# IsolatorPower.net
KiCad netlist of a schematic drawn in Altium Designer
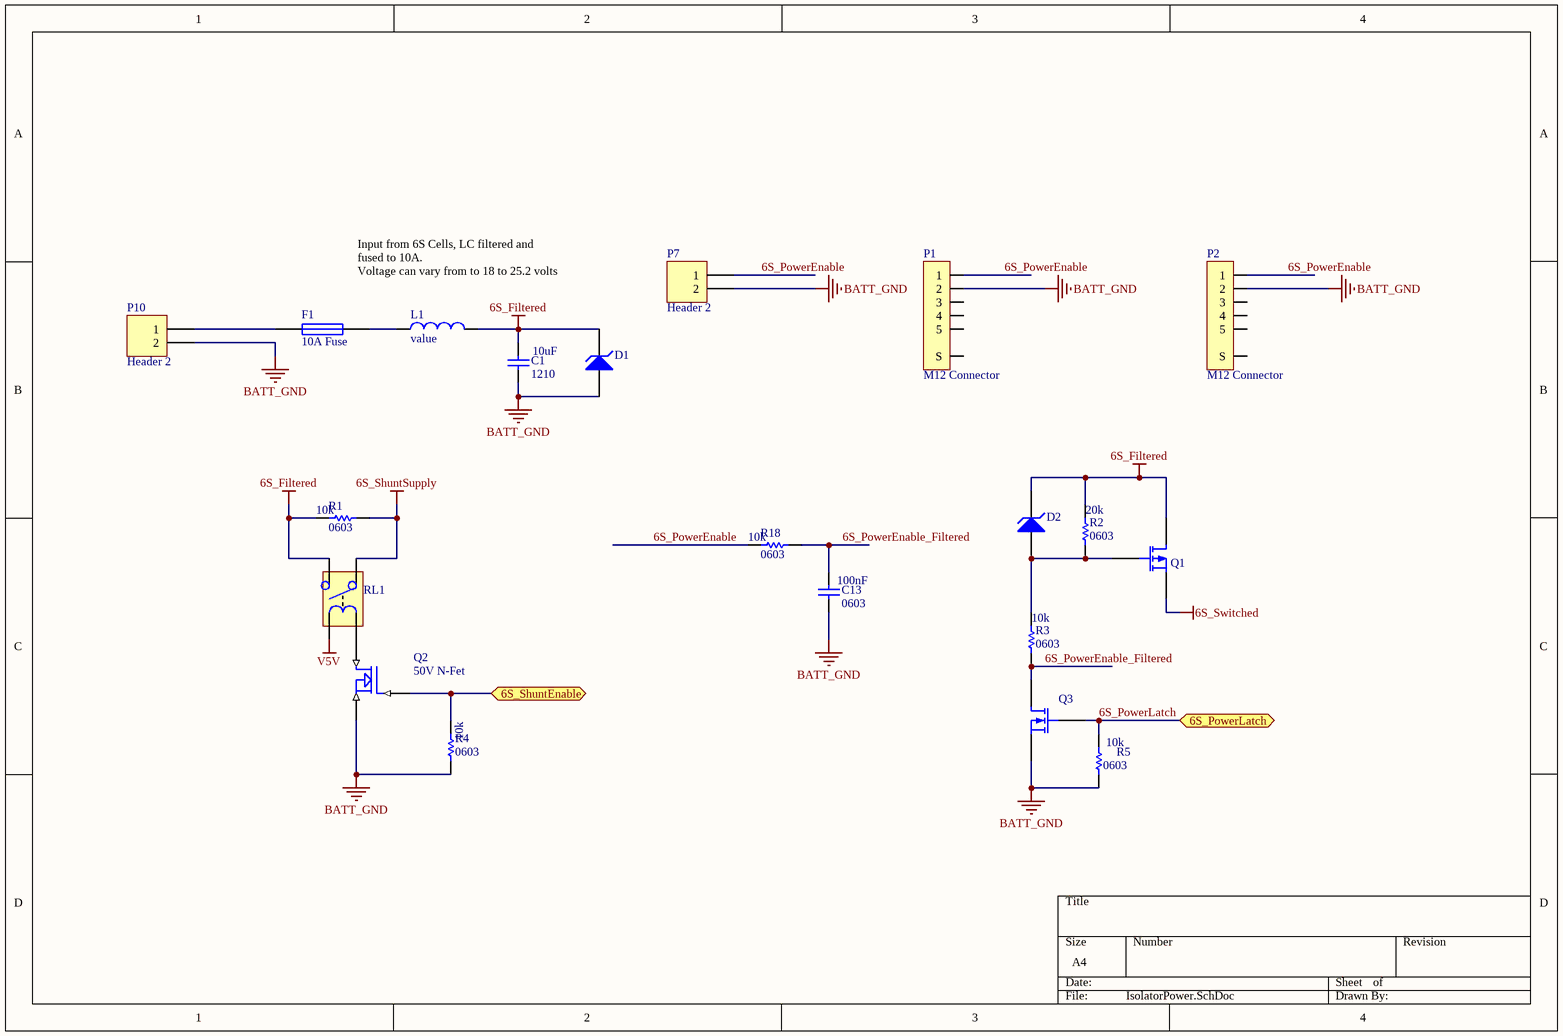
[diagram p0: IsolatorPower.SchDoc]

(export (version "E")
  (design (tool "Eeschema 10.0.6"))
  (components
    (comp (ref "C1")
      (value "10uF")
      (footprint "1210_M")
      (description "Default Capacitor")
      (fields (field (name "PACKAGE") "1210") (field (name "Comment") "C"))
      (libsource (lib "UNSW_LIB") (part "C"))
    )
    (comp (ref "C13")
      (value "100nF")
      (footprint "0603_M")
      (description "Default Capacitor")
      (fields (field (name "PACKAGE") "0603") (field (name "Comment") "C"))
      (libsource (lib "UNSW_LIB") (part "C"))
    )
    (comp (ref "D1")
      (value "~")
      (footprint "0805_M_POL")
      (description "Zener Diode")
      (libsource (lib "UNSW_LIB") (part "D Zener"))
    )
    (comp (ref "D2")
      (value "~")
      (footprint "0805_M_POL")
      (description "Zener Diode")
      (libsource (lib "UNSW_LIB") (part "D Zener"))
    )
    (comp (ref "F1")
      (value "10A Fuse")
      (footprint "LITTELFUSE-154")
      (description "Fuse")
      (libsource (lib "Miscellaneous") (part "FUSE"))
    )
    (comp (ref "L1")
      (value "value")
      (footprint "0805_M")
      (description "Inductor")
      (libsource (lib "UNSW_LIB") (part "L"))
    )
    (comp (ref "P1")
      (value "M12 Connector")
      (footprint "M12_5P_VERT")
      (description "5 Pin")
      (libsource (lib "UNSW_LIB") (part "M12 Connector"))
    )
    (comp (ref "P2")
      (value "M12 Connector")
      (footprint "M12_5P_VERT")
      (description "5 Pin")
      (libsource (lib "UNSW_LIB") (part "M12 Connector"))
    )
    (comp (ref "P7")
      (value "Header 2")
      (footprint "HDR1X2")
      (description "Header, 2-Pin")
      (fields (field (name "PUBLISHER") "Altium Limited"))
      (libsource (lib "Miscellaneous Connectors") (part "Header 2"))
    )
    (comp (ref "P10")
      (value "Header 2")
      (footprint "HDR1X2")
      (description "Header, 2-Pin")
      (fields (field (name "PUBLISHER") "Altium Limited"))
      (libsource (lib "Miscellaneous Connectors") (part "Header 2"))
    )
    (comp (ref "Q1")
      (value "PFET 40V 10A")
      (footprint "TO-252 (D-Pak)")
      (description "10A 40V")
      (libsource (lib "UNSW_LIB") (part "PFET 40V 10A"))
    )
    (comp (ref "Q2")
      (value "50V N-Fet")
      (footprint "SOT23-3")
      (description "1.7A, 20V N-Channel Enhancement mode FET")
      (libsource (lib "RCLDQ") (part "ZXM61N02F"))
    )
    (comp (ref "Q3")
      (value "NFET 30V 5A")
      (footprint "SOT23-3")
      (libsource (lib "UNSW_LIB") (part "NFET 30V 5A"))
    )
    (comp (ref "R1")
      (value "10k")
      (footprint "0603_M")
      (description "Resistor")
      (fields (field (name "PACKAGE") "0603") (field (name "Comment") "R"))
      (libsource (lib "UNSW_LIB") (part "R"))
    )
    (comp (ref "R2")
      (value "20k")
      (footprint "0603_M")
      (description "Resistor")
      (fields (field (name "PACKAGE") "0603") (field (name "Comment") "R"))
      (libsource (lib "UNSW_LIB") (part "R"))
    )
    (comp (ref "R3")
      (value "10k")
      (footprint "0603_M")
      (description "Resistor")
      (fields (field (name "PACKAGE") "0603") (field (name "Comment") "R"))
      (libsource (lib "UNSW_LIB") (part "R"))
    )
    (comp (ref "R4")
      (value "10k")
      (footprint "0603_M")
      (description "Resistor")
      (fields (field (name "PACKAGE") "0603") (field (name "Comment") "R"))
      (libsource (lib "UNSW_LIB") (part "R"))
    )
    (comp (ref "R5")
      (value "10k")
      (footprint "0603_M")
      (description "Resistor")
      (fields (field (name "PACKAGE") "0603") (field (name "Comment") "R"))
      (libsource (lib "UNSW_LIB") (part "R"))
    )
    (comp (ref "R18")
      (value "10k")
      (footprint "0603_M")
      (description "Resistor")
      (fields (field (name "PACKAGE") "0603") (field (name "Comment") "R"))
      (libsource (lib "UNSW_LIB") (part "R"))
    )
    (comp (ref "RL1")
      (value "Relay")
      (footprint "RELAY_G5Q_4PIN")
      (description "10A 30VDC Max Normally Open")
      (fields
        (field (name "MANUFACTURER") "Omron Electronics Inc-EMC Div")
        (field (name "MANUFACTURER PART NUMBER") "G5Q-1A4 DC5")
      )
      (libsource (lib "UNSW_LIB") (part "Relay"))
    )
  )
  (nets
    (net (code "1") (name "/6S_PowerEnable") (class "Default")
      (node (ref "P1") (pin "1") (pinfunction "1_1") (pintype "passive"))
      (node (ref "P2") (pin "1") (pinfunction "1_1") (pintype "passive"))
      (node (ref "P7") (pin "1") (pinfunction "1_1") (pintype "passive"))
      (node (ref "R18") (pin "2") (pinfunction "2_2") (pintype "passive"))
    )
    (net (code "2") (name "/6S_PowerEnable_Filtered") (class "Default")
      (node (ref "C13") (pin "1") (pinfunction "1_1") (pintype "passive"))
      (node (ref "Q3") (pin "3") (pinfunction "D_3") (pintype "passive"))
      (node (ref "R18") (pin "1") (pinfunction "1_1") (pintype "passive"))
      (node (ref "R3") (pin "1") (pinfunction "1_1") (pintype "passive"))
    )
    (net (code "3") (name "/6S_PowerLatch") (class "Default")
      (node (ref "Q3") (pin "1") (pinfunction "G_1") (pintype "passive"))
      (node (ref "R5") (pin "2") (pinfunction "2_2") (pintype "passive"))
    )
    (net (code "4") (name "/6S_ShuntEnable") (class "Default")
      (node (ref "Q2") (pin "1") (pinfunction "G_1") (pintype "input"))
      (node (ref "R4") (pin "2") (pinfunction "2_2") (pintype "passive"))
    )
    (net (code "5") (name "6S_Filtered") (class "Default")
      (node (ref "C1") (pin "1") (pinfunction "1_1") (pintype "passive"))
      (node (ref "D1") (pin "2") (pinfunction "K_2") (pintype "passive"))
      (node (ref "D2") (pin "2") (pinfunction "K_2") (pintype "passive"))
      (node (ref "L1") (pin "2") (pinfunction "B_2") (pintype "passive"))
      (node (ref "Q1") (pin "1") (pinfunction "D_1") (pintype "passive"))
      (node (ref "R1") (pin "2") (pinfunction "2_2") (pintype "passive"))
      (node (ref "R2") (pin "2") (pinfunction "2_2") (pintype "passive"))
      (node (ref "RL1") (pin "2") (pinfunction "2_2") (pintype "passive"))
    )
    (net (code "6") (name "6S_ShuntSupply") (class "Default")
      (node (ref "R1") (pin "1") (pinfunction "1_1") (pintype "passive"))
      (node (ref "RL1") (pin "3") (pinfunction "3_3") (pintype "passive"))
    )
    (net (code "7") (name "6S_Switched") (class "Default")
      (node (ref "Q1") (pin "3") (pinfunction "S_3") (pintype "passive"))
    )
    (net (code "8") (name "BATT_GND") (class "Default")
      (node (ref "C1") (pin "2") (pinfunction "2_2") (pintype "passive"))
      (node (ref "C13") (pin "2") (pinfunction "2_2") (pintype "passive"))
      (node (ref "D1") (pin "1") (pinfunction "A_1") (pintype "passive"))
      (node (ref "P1") (pin "2") (pinfunction "2_2") (pintype "passive"))
      (node (ref "P10") (pin "2") (pinfunction "2_2") (pintype "passive"))
      (node (ref "P2") (pin "2") (pinfunction "2_2") (pintype "passive"))
      (node (ref "P7") (pin "2") (pinfunction "2_2") (pintype "passive"))
      (node (ref "Q2") (pin "2") (pinfunction "S_2") (pintype "input"))
      (node (ref "Q3") (pin "2") (pinfunction "S_2") (pintype "passive"))
      (node (ref "R4") (pin "1") (pinfunction "1_1") (pintype "passive"))
      (node (ref "R5") (pin "1") (pinfunction "1_1") (pintype "passive"))
    )
    (net (code "9") (name "Net-(D2-A)") (class "Default")
      (node (ref "D2") (pin "1") (pinfunction "A_1") (pintype "passive"))
      (node (ref "Q1") (pin "2") (pinfunction "G_2") (pintype "passive"))
      (node (ref "R2") (pin "1") (pinfunction "1_1") (pintype "passive"))
      (node (ref "R3") (pin "2") (pinfunction "2_2") (pintype "passive"))
    )
    (net (code "10") (name "Net-(F1-Pad1)") (class "Default")
      (node (ref "F1") (pin "1") (pinfunction "1_1") (pintype "passive"))
      (node (ref "P10") (pin "1") (pinfunction "1_1") (pintype "passive"))
    )
    (net (code "11") (name "Net-(L1-A)") (class "Default")
      (node (ref "F1") (pin "2") (pinfunction "2_2") (pintype "passive"))
      (node (ref "L1") (pin "1") (pinfunction "A_1") (pintype "passive"))
    )
    (net (code "12") (name "Net-(Q2-D)") (class "Default")
      (node (ref "Q2") (pin "3") (pinfunction "D_3") (pintype "input"))
      (node (ref "RL1") (pin "5") (pinfunction "5_5") (pintype "passive"))
    )
    (net (code "13") (name "V5V") (class "Default")
      (node (ref "RL1") (pin "1") (pinfunction "1_1") (pintype "passive"))
    )
    (net (code "14") (name "unconnected-(P1-Pad3)") (class "Default")
      (node (ref "P1") (pin "3") (pinfunction "3_3") (pintype "passive"))
    )
    (net (code "15") (name "unconnected-(P1-Pad4)") (class "Default")
      (node (ref "P1") (pin "4") (pinfunction "4_4") (pintype "passive"))
    )
    (net (code "16") (name "unconnected-(P1-Pad5)") (class "Default")
      (node (ref "P1") (pin "5") (pinfunction "5_5") (pintype "passive"))
    )
    (net (code "17") (name "unconnected-(P1-PadS)") (class "Default")
      (node (ref "P1") (pin "S") (pinfunction "S_S") (pintype "passive"))
    )
    (net (code "18") (name "unconnected-(P2-Pad3)") (class "Default")
      (node (ref "P2") (pin "3") (pinfunction "3_3") (pintype "passive"))
    )
    (net (code "19") (name "unconnected-(P2-Pad4)") (class "Default")
      (node (ref "P2") (pin "4") (pinfunction "4_4") (pintype "passive"))
    )
    (net (code "20") (name "unconnected-(P2-Pad5)") (class "Default")
      (node (ref "P2") (pin "5") (pinfunction "5_5") (pintype "passive"))
    )
    (net (code "21") (name "unconnected-(P2-PadS)") (class "Default")
      (node (ref "P2") (pin "S") (pinfunction "S_S") (pintype "passive"))
    )
  )
)
